# pressure-sensor-mpxv7007.net
KiCad netlist of a schematic drawn in EAGLE
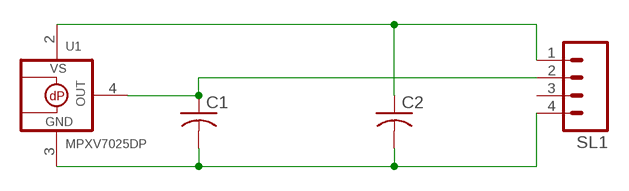
[diagram p0: schematic, sheet 1]

(export (version "E")
  (design (tool "Eeschema 10.0.6"))
  (components
    (comp (ref "C1")
      (value "C-USC0805")
      (footprint "eagle-import:C0805")
      (libsource (lib "eagle-import") (part "C-USC0805"))
    )
    (comp (ref "C2")
      (value "C-USC0603")
      (footprint "eagle-import:C0603")
      (libsource (lib "eagle-import") (part "adafruit_420_C-USC0603"))
    )
    (comp (ref "SL1")
      (value "M04")
      (footprint "eagle-import:04P")
      (libsource (lib "eagle-import") (part "M04"))
    )
    (comp (ref "U1")
      (value "MPXV7025DP")
      (footprint "eagle-import:SOP8-1351")
      (fields (field (name "MF") "Freescale Semiconductor"))
      (libsource (lib "eagle-import") (part "MPXV7025DP"))
    )
  )
  (nets
    (net (code "1") (name "Net-(U1-+VOUT)") (class "Default")
      (node (ref "C1") (pin "1") (pinfunction "1_1") (pintype "passive"))
      (node (ref "SL1") (pin "2") (pinfunction "2_2") (pintype "passive"))
      (node (ref "U1") (pin "4") (pinfunction "+VOUT_4") (pintype "output"))
    )
    (net (code "2") (name "Net-(U1-GND)") (class "Default")
      (node (ref "C1") (pin "2") (pinfunction "2_2") (pintype "passive"))
      (node (ref "C2") (pin "2") (pinfunction "2_2") (pintype "passive"))
      (node (ref "SL1") (pin "4") (pinfunction "4_4") (pintype "passive"))
      (node (ref "U1") (pin "3") (pinfunction "GND_3") (pintype "power_in"))
    )
    (net (code "3") (name "Net-(U1-VS)") (class "Default")
      (node (ref "C2") (pin "1") (pinfunction "1_1") (pintype "passive"))
      (node (ref "SL1") (pin "1") (pinfunction "1_1") (pintype "passive"))
      (node (ref "U1") (pin "2") (pinfunction "VS_2") (pintype "power_in"))
    )
    (net (code "4") (name "unconnected-(SL1-Pad3)") (class "Default")
      (node (ref "SL1") (pin "3") (pinfunction "3_3") (pintype "passive"))
    )
  )
)
